# Sheet2.net
KiCad netlist of a schematic drawn in Altium Designer
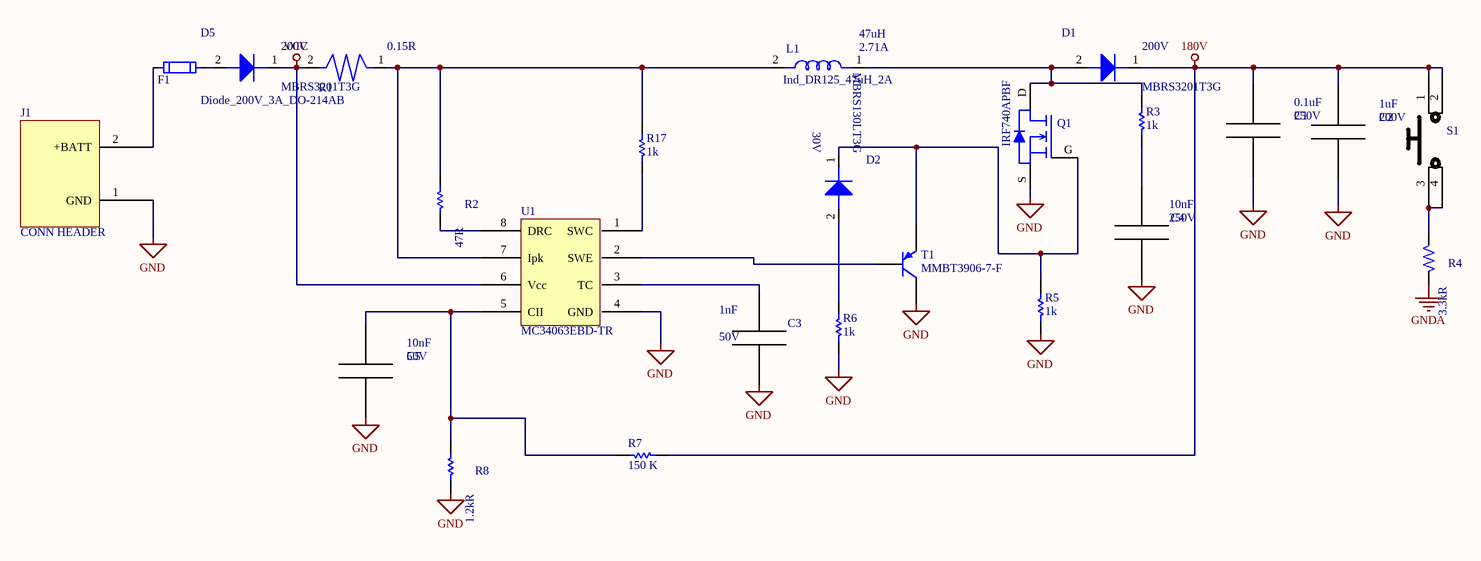
[diagram p0: Sheet2.SchDoc]

(export (version "E")
  (design (tool "Eeschema 10.0.6"))
  (components
    (comp (ref "C1")
      (value "Cap_Cer_0.1u_250V_1206")
      (footprint "CAP_CER_0.1U_250V_1206")
      (description "KEMET - C1206C104KARACTU - CAP, 0.1µF, 250V, 10%, X7R, 1206")
      (fields
        (field (name "MANUFACTURER") "KEMET")
        (field (name "MANUFACTURER PART NUMBER") "C1206C104KARACTU")
      )
      (libsource (lib "Capacitors") (part "Cap_Cer_0.1u_250V_1206"))
    )
    (comp (ref "C2")
      (value "Cap_Cer_1u_200V_2225")
      (footprint "Cap_Cer_1u_200V_2225")
      (description "CAP CER 1UF 200V X7R 2225")
      (fields
        (field (name "MANUFACTURER") "Vishay Vitramon")
        (field (name "MANUFACTURER PART NUMBER") "VJ2225Y105KXCAT")
      )
      (libsource (lib "Capacitors") (part "Cap_Cer_1u_200V_2225"))
    )
    (comp (ref "C3")
      (value "Cap_Cer_1n_50V_0603")
      (footprint "Cap_Cer 1n_50V_0603")
      (description "MURATA - GRM188R71H102KA01D - CAP, MLCC, X7R, 1NF, 50V, 0603, REEL")
      (fields
        (field (name "MANUFACTURER") "Murata")
        (field (name "MANUFACTURER PART NUMBER") "GRM188R71H102KA01D")
      )
      (libsource (lib "Capacitors") (part "Cap_Cer_1n_50V_0603"))
    )
    (comp (ref "C4")
      (value "Cap_Cer_10nF_250V_0805")
      (footprint "CAP_CER_10N_250V_0805")
      (description "Capacitors; Ceramic SMT; Tip and Ring; .010uF 250V; 10%; X7R; TR")
      (fields
        (field (name "MANUFACTURER") "KEMET")
        (field (name "MANUFACTURER PART NUMBER") "C0805C103KARACTU")
      )
      (libsource (lib "Capacitors") (part "Cap_Cer_10nF_250V_0805"))
    )
    (comp (ref "C5")
      (value "Cap_Cer_10n_50V_0603")
      (footprint "Cap_Cer_10n_50V_0603")
      (fields
        (field (name "MANUFACTURER") "Murata")
        (field (name "MANUFACTURER PART NUMBER") "GRM188R71H103KA01D")
        (field (name "TOLERANCE") "10%")
      )
      (libsource (lib "Capacitors") (part "Cap_Cer_10n_50V_0603"))
    )
    (comp (ref "D1")
      (value "Diode_200V_3A_DO-214AB")
      (footprint "D320")
      (fields
        (field (name "MANUFACTURER") "ON Semiconductor")
        (field (name "MANUFACTURER PART NUMBER") "MBRS3201T3G")
      )
      (libsource (lib "Schlib1") (part "Diode_200V_3A_DO-214AB"))
    )
    (comp (ref "D2")
      (value "Diode_30V_2A_DO_214AA")
      (footprint "D130")
      (fields
        (field (name "MANUFACTURER") "ON Semiconductor")
        (field (name "MANUFACTURER PART NUMBER") "MBRS130LT3G")
      )
      (libsource (lib "Schlib1") (part "Diode_30V_2A_DO_214AA"))
    )
    (comp (ref "D5")
      (value "Diode_200V_3A_DO-214AB")
      (footprint "D320")
      (fields
        (field (name "MANUFACTURER") "ON Semiconductor")
        (field (name "MANUFACTURER PART NUMBER") "MBRS3201T3G")
      )
      (libsource (lib "Schlib1") (part "Diode_200V_3A_DO-214AB"))
    )
    (comp (ref "F1")
      (value "Fuseholder(Cartridge)")
      (footprint "FuseHolder")
      (description "Fuse Holder 10A 500VDC Solder Pin Through Hole Bulk Cartridge")
      (fields (field (name "MANUFACTURER") "Schurter") (field (name "MANUFACTURER PART NUMBER") "00318201"))
      (libsource (lib "fuse_holder") (part "Fuseholder(Cartridge)"))
    )
    (comp (ref "J1")
      (value "CONN HEADER")
      (footprint "CONN HEADER R_A 2POS 2.54MM")
      (description "Conn Wire to Board HDR 2 POS 2.54mm Solder RA Thru-Hole Bag")
      (libsource (lib "kicker_andrei") (part "CONN HEADER R_A 2POS 2.54MM"))
    )
    (comp (ref "L1")
      (value "Ind_DR125_47uH_2A")
      (footprint "DR125")
      (description "FIXED IND 47UH 2.71A 74 MOHM SMD")
      (fields
        (field (name "MANUFACTURER") "Eaton Cooper")
        (field (name "MANUFACTURER PART NUMBER") "DR125-470-R")
      )
      (libsource (lib "Schlib1") (part "Ind_DR125_47uH_2A"))
    )
    (comp (ref "Q1")
      (value "IRF740APBF")
      (footprint "To-220")
      (fields (field (name "MANUFACTURER") "Vishay"))
      (libsource (lib "Transistors") (part "IRF740APBF"))
    )
    (comp (ref "R1")
      (value "RES_0.15R_2W_2512")
      (footprint "R2512")
      (fields
        (field (name "MANUFACTURER") "TE Connectivity")
        (field (name "MANUFACTURER PART NUMBER") "RLP73K3AR15JTE")
        (field (name "TOLERANCE") "5%")
      )
      (libsource (lib "Schlib1") (part "RES_0.15R_2W_2512"))
    )
    (comp (ref "R2")
      (value "Res_47R_0805")
      (footprint "0805")
      (description "RES SMD 47 OHM 5% 1/8W 0805")
      (fields
        (field (name "MANUFACTURER") "Stackpole Electronics")
        (field (name "MANUFACTURER PART NUMBER") "RMCF0805JT47R0")
      )
      (libsource (lib "Resistors") (part "Res_47R_0805"))
    )
    (comp (ref "R3")
      (value "1k")
      (footprint "Resistor_0805")
      (description "RES SMD 0805 1k 1/8W")
      (libsource (lib "Resistors") (part "Res_1k_0805"))
    )
    (comp (ref "R4")
      (value "3.3K OHMS 2512")
      (footprint "RESISTOR_2512")
      (description "RES SMD 3.3K OHM 1% 2W 2512")
      (fields (field (name "TOLERANCE") "1%"))
      (libsource (lib "kicker_andrei") (part "RES 3.3K OHM 2512"))
    )
    (comp (ref "R5")
      (value "1k")
      (footprint "Resistor_0805")
      (description "RES SMD 0805 1k 1/8W")
      (libsource (lib "Resistors") (part "Res_1k_0805"))
    )
    (comp (ref "R6")
      (value "1k")
      (footprint "Resistor_0805")
      (description "RES SMD 0805 1k 1/8W")
      (libsource (lib "Resistors") (part "Res_1k_0805"))
    )
    (comp (ref "R7")
      (value "150 K")
      (footprint "Resistor_0805")
      (description "RES SMD 150K 0.125W 0805")
      (libsource (lib "Resistors") (part "Res_150k_0805"))
    )
    (comp (ref "R8")
      (value "Res_1.2K_0805_1%")
      (footprint "0805")
      (description "PANASONIC ELECTRONIC COMPONENTS - ERJ6ENF1201V - RES, THICK FILM, 1K2, 125MW, 1%, REEL")
      (fields
        (field (name "MANUFACTURER") "Panasonic")
        (field (name "MANUFACTURER PART NUMBER") "ERJ-6ENF1201V")
      )
      (libsource (lib "Resistors") (part "Res_1.2K_0805_1%"))
    )
    (comp (ref "R17")
      (value "1k")
      (footprint "Resistor_0805")
      (description "RES SMD 0805 1k 1/8W")
      (libsource (lib "Resistors") (part "Res_1k_0805"))
    )
    (comp (ref "S1")
      (value "B3F-1005")
      (footprint "SWITCH_TACTILE_SPST-NO_0.05A_24V")
      (description "Switch Tactile N.O. SPST Flat Plunger PC Pins 0.05A 24VDC 2.55N Thru-Hole Bag")
      (fields (field (name "MANUFACTURER") "Omron"))
      (libsource (lib "Switches") (part "B3F-1005"))
    )
    (comp (ref "T1")
      (value "MMBT3906-7-F")
      (footprint "SOT-23-3")
      (description "TRANS PNP 40V 0.2A SOT23-3")
      (fields (field (name "MANUFACTURER") "Diodes Zetex"))
      (libsource (lib "Transistors") (part "MMBT3906-7-F"))
    )
    (comp (ref "U1")
      (value "MC34063EBD-TR")
      (footprint "MC34063EBD-TR")
      (description "Conv DC-DC Step Down/Step Up 3V to 40V 8-Pin SO N T/R")
      (fields (field (name "MANUFACTURER") "STMicroelectronics"))
      (libsource (lib "Regulators") (part "MC34063EBD-TR"))
    )
  )
  (nets
    (net (code "1") (name "180V") (class "Default")
      (node (ref "C1") (pin "1") (pintype "passive"))
      (node (ref "C2") (pin "1") (pintype "passive"))
      (node (ref "D1") (pin "1") (pinfunction "1_1") (pintype "passive"))
      (node (ref "R7") (pin "1") (pinfunction "1_1") (pintype "passive"))
      (node (ref "S1") (pin "1") (pinfunction "1_1") (pintype "passive"))
      (node (ref "S1") (pin "2") (pinfunction "2_2") (pintype "passive"))
    )
    (net (code "2") (name "GND") (class "Default")
      (node (ref "C1") (pin "2") (pintype "passive"))
      (node (ref "C2") (pin "2") (pintype "passive"))
      (node (ref "C3") (pin "2") (pintype "passive"))
      (node (ref "C4") (pin "2") (pintype "passive"))
      (node (ref "C5") (pin "2") (pintype "passive"))
      (node (ref "J1") (pin "1") (pinfunction "GND_1") (pintype "passive"))
      (node (ref "Q1") (pin "S") (pinfunction "S_S") (pintype "passive"))
      (node (ref "R5") (pin "1") (pinfunction "1_1") (pintype "passive"))
      (node (ref "R6") (pin "1") (pinfunction "1_1") (pintype "passive"))
      (node (ref "R8") (pin "1") (pinfunction "1_1") (pintype "passive"))
      (node (ref "T1") (pin "C") (pinfunction "C_C") (pintype "passive"))
      (node (ref "U1") (pin "4") (pinfunction "GND_4") (pintype "passive"))
    )
    (net (code "3") (name "GNDA") (class "Default")
      (node (ref "R4") (pin "2") (pinfunction "2_2") (pintype "passive"))
    )
    (net (code "4") (name "Net-(C4-Pad1)") (class "Default")
      (node (ref "C4") (pin "1") (pintype "passive"))
      (node (ref "R3") (pin "1") (pinfunction "1_1") (pintype "passive"))
    )
    (net (code "5") (name "Net-(D1-Pad2)") (class "Default")
      (node (ref "D1") (pin "2") (pinfunction "2_2") (pintype "passive"))
      (node (ref "L1") (pin "1") (pinfunction "1_1") (pintype "passive"))
      (node (ref "Q1") (pin "D") (pinfunction "D_D") (pintype "passive"))
      (node (ref "R3") (pin "2") (pinfunction "2_2") (pintype "passive"))
    )
    (net (code "6") (name "Net-(D2-Pad1)") (class "Default")
      (node (ref "D2") (pin "1") (pinfunction "1_1") (pintype "passive"))
      (node (ref "Q1") (pin "G") (pinfunction "G_G") (pintype "passive"))
      (node (ref "R5") (pin "2") (pinfunction "2_2") (pintype "passive"))
      (node (ref "T1") (pin "E") (pinfunction "E_E") (pintype "passive"))
    )
    (net (code "7") (name "Net-(D2-Pad2)") (class "Default")
      (node (ref "D2") (pin "2") (pinfunction "2_2") (pintype "passive"))
      (node (ref "R6") (pin "2") (pinfunction "2_2") (pintype "passive"))
    )
    (net (code "8") (name "Net-(D5-Pad2)") (class "Default")
      (node (ref "D5") (pin "2") (pinfunction "2_2") (pintype "passive"))
      (node (ref "F1") (pin "1") (pinfunction "1_1") (pintype "passive"))
    )
    (net (code "9") (name "Net-(J1-+BATT)") (class "Default")
      (node (ref "F1") (pin "2") (pinfunction "2_2") (pintype "passive"))
      (node (ref "J1") (pin "2") (pinfunction "+BATT_2") (pintype "passive"))
    )
    (net (code "10") (name "Net-(R4-Pad1)") (class "Default")
      (node (ref "R4") (pin "1") (pinfunction "1_1") (pintype "passive"))
      (node (ref "S1") (pin "3") (pinfunction "3_3") (pintype "passive"))
      (node (ref "S1") (pin "4") (pinfunction "4_4") (pintype "passive"))
    )
    (net (code "11") (name "Net-(U1-CII)") (class "Default")
      (node (ref "C5") (pin "1") (pintype "passive"))
      (node (ref "R7") (pin "2") (pinfunction "2_2") (pintype "passive"))
      (node (ref "R8") (pin "2") (pinfunction "2_2") (pintype "passive"))
      (node (ref "U1") (pin "5") (pinfunction "CII_5") (pintype "passive"))
    )
    (net (code "12") (name "Net-(U1-DRC)") (class "Default")
      (node (ref "R2") (pin "1") (pinfunction "1_1") (pintype "passive"))
      (node (ref "U1") (pin "8") (pinfunction "DRC_8") (pintype "passive"))
    )
    (net (code "13") (name "Net-(U1-Ipk)") (class "Default")
      (node (ref "L1") (pin "2") (pinfunction "2_2") (pintype "passive"))
      (node (ref "R1") (pin "1") (pinfunction "1_1") (pintype "passive"))
      (node (ref "R17") (pin "2") (pinfunction "2_2") (pintype "passive"))
      (node (ref "R2") (pin "2") (pinfunction "2_2") (pintype "passive"))
      (node (ref "U1") (pin "7") (pinfunction "Ipk_7") (pintype "passive"))
    )
    (net (code "14") (name "Net-(U1-SWC)") (class "Default")
      (node (ref "R17") (pin "1") (pinfunction "1_1") (pintype "passive"))
      (node (ref "U1") (pin "1") (pinfunction "SWC_1") (pintype "passive"))
    )
    (net (code "15") (name "Net-(U1-SWE)") (class "Default")
      (node (ref "T1") (pin "B") (pinfunction "B_B") (pintype "passive"))
      (node (ref "U1") (pin "2") (pinfunction "SWE_2") (pintype "passive"))
    )
    (net (code "16") (name "Net-(U1-TC)") (class "Default")
      (node (ref "C3") (pin "1") (pintype "passive"))
      (node (ref "U1") (pin "3") (pinfunction "TC_3") (pintype "passive"))
    )
    (net (code "17") (name "VCC") (class "Default")
      (node (ref "D5") (pin "1") (pinfunction "1_1") (pintype "passive"))
      (node (ref "R1") (pin "2") (pinfunction "2_2") (pintype "passive"))
      (node (ref "U1") (pin "6") (pinfunction "Vcc_6") (pintype "passive"))
    )
  )
)
